# carte_pami2026.net
KiCad netlist of a schematic drawn in Altium Designer
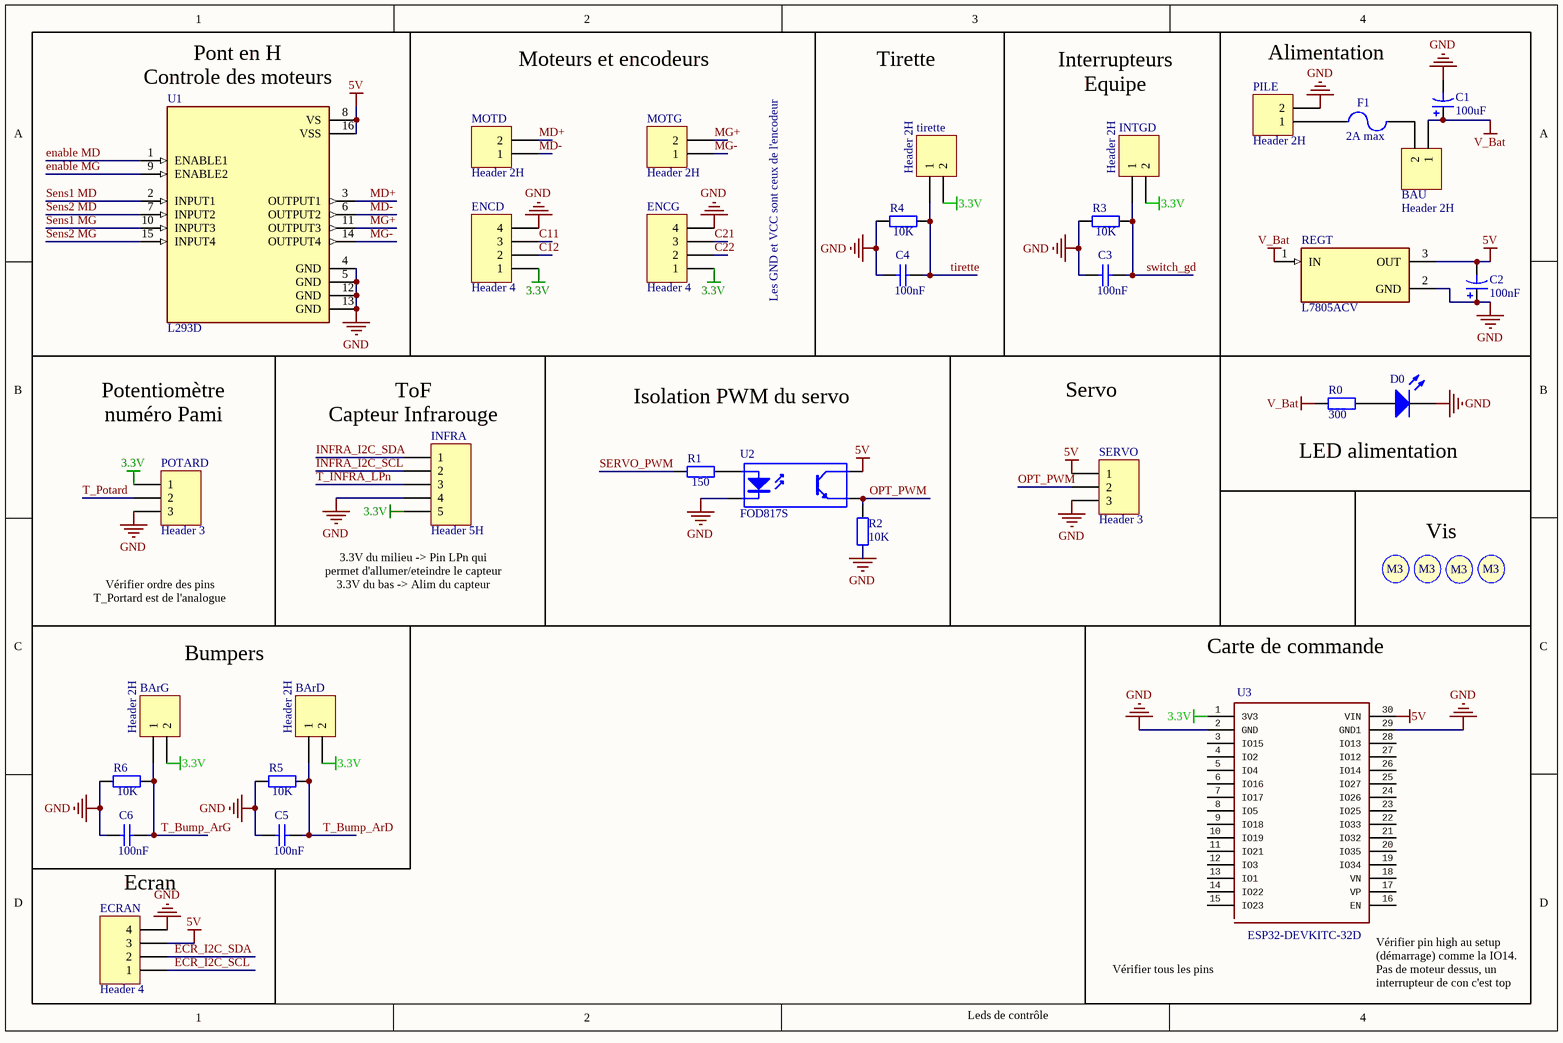
[diagram p0: carte_pami2026.SchDoc]

(export (version "E")
  (design (tool "Eeschema 10.0.6"))
  (components
    (comp (ref "BArD")
      (value "Header 2H")
      (footprint "JST_B2B-XH-A_(LF)(SN)")
      (description "Header, 2-Pin, Right Angle")
      (fields (field (name "PUBLISHER") "Altium Limited"))
      (libsource (lib "Miscellaneous Connectors") (part "Header 2H"))
    )
    (comp (ref "BArG")
      (value "Header 2H")
      (footprint "JST_B2B-XH-A_(LF)(SN)")
      (description "Header, 2-Pin, Right Angle")
      (fields (field (name "PUBLISHER") "Altium Limited"))
      (libsource (lib "Miscellaneous Connectors") (part "Header 2H"))
    )
    (comp (ref "BAU")
      (value "Header 2H")
      (footprint "JST_B2B-XH-A_(LF)(SN)")
      (description "Header, 2-Pin, Right Angle")
      (fields (field (name "PUBLISHER") "Altium Limited"))
      (libsource (lib "") (part "Header 2H_2"))
    )
    (comp (ref "C1")
      (value "100uF")
      (footprint "Condensateur")
      (description "Polarized Capacitor (Radial)")
      (fields (field (name "Comment") "35V") (field (name "PUBLISHER") "Altium Limited"))
      (libsource (lib "Miscellaneous Devices") (part "Cap Pol1"))
    )
    (comp (ref "C2")
      (value "100nF")
      (footprint "Condensateur")
      (description "Polarized Capacitor (Radial)")
      (fields (field (name "Comment") "35V") (field (name "PUBLISHER") "Altium Limited"))
      (libsource (lib "Miscellaneous Devices") (part "Cap Pol1"))
    )
    (comp (ref "C3")
      (value "100nF")
      (footprint "Capacitor 1206")
      (description "Capacitor")
      (fields (field (name "Comment") "Cap") (field (name "PUBLISHER") "Altium Limited"))
      (libsource (lib "Miscellaneous Devices") (part "Cap"))
    )
    (comp (ref "C4")
      (value "100nF")
      (footprint "Capacitor 1206")
      (description "Capacitor")
      (fields (field (name "Comment") "Cap") (field (name "PUBLISHER") "Altium Limited"))
      (libsource (lib "Miscellaneous Devices") (part "Cap"))
    )
    (comp (ref "C5")
      (value "100nF")
      (footprint "Capacitor 1206")
      (description "Capacitor")
      (fields (field (name "Comment") "Cap") (field (name "PUBLISHER") "Altium Limited"))
      (libsource (lib "Miscellaneous Devices") (part "Cap"))
    )
    (comp (ref "C6")
      (value "100nF")
      (footprint "Capacitor 1206")
      (description "Capacitor")
      (fields (field (name "Comment") "Cap") (field (name "PUBLISHER") "Altium Limited"))
      (libsource (lib "Miscellaneous Devices") (part "Cap"))
    )
    (comp (ref "D0")
      (value "L")
      (footprint "KP-3216SEC")
      (description "Typical RED, GREEN, YELLOW, AMBER GaAs LED")
      (fields (field (name "PUBLISHER") "Altium Limited"))
      (libsource (lib "Miscellaneous Devices") (part "LED2"))
    )
    (comp (ref "ECRAN")
      (value "Header 4")
      (footprint "B4BXHALFSN")
      (description "Header, 4-Pin")
      (fields (field (name "PUBLISHER") "Altium Limited"))
      (libsource (lib "Miscellaneous Connectors") (part "Header 4"))
    )
    (comp (ref "ENCD")
      (value "Header 4")
      (footprint "B4BXHALFSN")
      (description "Header, 4-Pin")
      (fields (field (name "PUBLISHER") "Altium Limited"))
      (libsource (lib "Miscellaneous Connectors") (part "Header 4"))
    )
    (comp (ref "ENCG")
      (value "Header 4")
      (footprint "B4BXHALFSN")
      (description "Header, 4-Pin")
      (fields (field (name "PUBLISHER") "Altium Limited"))
      (libsource (lib "Miscellaneous Connectors") (part "Header 4"))
    )
    (comp (ref "F1")
      (value "2A max")
      (footprint "Fuse")
      (description "Main Fuse")
      (fields (field (name "PUBLISHER") "Altium Limited"))
      (libsource (lib "Miscellaneous Devices") (part "Fuse 2"))
    )
    (comp (ref "INFRA")
      (value "Header 5H")
      (footprint "B5BXHAMLFSN")
      (description "Header, 5-Pin, Right Angle")
      (fields (field (name "PUBLISHER") "Altium Limited"))
      (libsource (lib "Miscellaneous Connectors") (part "Header 5H"))
    )
    (comp (ref "INTGD")
      (value "Header 2H")
      (footprint "JST_B2B-XH-A_(LF)(SN)")
      (description "Header, 2-Pin, Right Angle")
      (fields (field (name "PUBLISHER") "Altium Limited"))
      (libsource (lib "Miscellaneous Connectors") (part "Header 2H"))
    )
    (comp (ref "MOTD")
      (value "Header 2H")
      (footprint "JST_B2B-XH-A_(LF)(SN)")
      (description "Header, 2-Pin, Right Angle")
      (fields (field (name "PUBLISHER") "Altium Limited"))
      (libsource (lib "") (part "Header 2H_1"))
    )
    (comp (ref "MOTG")
      (value "Header 2H")
      (footprint "JST_B2B-XH-A_(LF)(SN)")
      (description "Header, 2-Pin, Right Angle")
      (fields (field (name "PUBLISHER") "Altium Limited"))
      (libsource (lib "") (part "Header 2H_1"))
    )
    (comp (ref "PILE")
      (value "Header 2H")
      (footprint "JST_B2B-XH-A_(LF)(SN)")
      (description "Header, 2-Pin, Right Angle")
      (fields (field (name "PUBLISHER") "Altium Limited"))
      (libsource (lib "") (part "Header 2H_1"))
    )
    (comp (ref "POTARD")
      (value "Header 3")
      (footprint "JST_B3B-XH-A(LF)(SN)")
      (description "Header, 3-Pin")
      (fields (field (name "PUBLISHER") "Altium Limited"))
      (libsource (lib "Miscellaneous Connectors") (part "Header 3"))
    )
    (comp (ref "R0")
      (value "300")
      (footprint "Resistor 1206")
      (description "Resistor")
      (fields (field (name "Comment") "Res2") (field (name "PUBLISHER") "Altium Limited"))
      (libsource (lib "Miscellaneous Devices") (part "Res2"))
    )
    (comp (ref "R1")
      (value "150")
      (footprint "Resistor 1206")
      (description "Resistor")
      (fields (field (name "Comment") "Res2") (field (name "PUBLISHER") "Altium Limited"))
      (libsource (lib "Miscellaneous Devices") (part "Res2"))
    )
    (comp (ref "R2")
      (value "10K")
      (footprint "Resistor 1206")
      (description "Resistor")
      (fields (field (name "Comment") "Res2") (field (name "PUBLISHER") "Altium Limited"))
      (libsource (lib "") (part "Res2_1"))
    )
    (comp (ref "R3")
      (value "10K")
      (footprint "Resistor 1206")
      (description "Resistor")
      (fields (field (name "Comment") "Res2") (field (name "PUBLISHER") "Altium Limited"))
      (libsource (lib "Miscellaneous Devices") (part "Res2"))
    )
    (comp (ref "R4")
      (value "10K")
      (footprint "Resistor 1206")
      (description "Resistor")
      (fields (field (name "Comment") "Res2") (field (name "PUBLISHER") "Altium Limited"))
      (libsource (lib "Miscellaneous Devices") (part "Res2"))
    )
    (comp (ref "R5")
      (value "10K")
      (footprint "Resistor 1206")
      (description "Resistor")
      (fields (field (name "Comment") "Res2") (field (name "PUBLISHER") "Altium Limited"))
      (libsource (lib "Miscellaneous Devices") (part "Res2"))
    )
    (comp (ref "R6")
      (value "10K")
      (footprint "Resistor 1206")
      (description "Resistor")
      (fields (field (name "Comment") "Res2") (field (name "PUBLISHER") "Altium Limited"))
      (libsource (lib "Miscellaneous Devices") (part "Res2"))
    )
    (comp (ref "REGT")
      (value "L7805ACV")
      (footprint "TO254P460X1020X1945-3P")
      (description "Linear Voltage Regulator IC Positive Fixed 1 Output 1.5A TO-220")
      (fields (field (name "MF") "STMicroelectronics"))
      (libsource (lib "L7805ACV") (part "L7805ACV"))
    )
    (comp (ref "S1")
      (value "Screw M3")
      (footprint "Screw M3")
      (libsource (lib "Robot_2019") (part "Screw M3"))
    )
    (comp (ref "S2")
      (value "Screw M3")
      (footprint "Screw M3")
      (libsource (lib "Robot_2019") (part "Screw M3"))
    )
    (comp (ref "S3")
      (value "Screw M3")
      (footprint "Screw M3")
      (libsource (lib "Robot_2019") (part "Screw M3"))
    )
    (comp (ref "S4")
      (value "Screw M3")
      (footprint "Screw M3")
      (libsource (lib "Robot_2019") (part "Screw M3"))
    )
    (comp (ref "SERVO")
      (value "Header 3")
      (footprint "JST_B3B-XH-A(LF)(SN)")
      (description "Header, 3-Pin")
      (fields (field (name "PUBLISHER") "Altium Limited"))
      (libsource (lib "Miscellaneous Connectors") (part "Header 3"))
    )
    (comp (ref "tirette")
      (value "Header 2H")
      (footprint "JST_B2B-XH-A_(LF)(SN)")
      (description "Header, 2-Pin, Right Angle")
      (fields (field (name "PUBLISHER") "Altium Limited"))
      (libsource (lib "Miscellaneous Connectors") (part "Header 2H"))
    )
    (comp (ref "U1")
      (value "L293D")
      (footprint "DIP880W50P254L2000H510Q16")
      (description "Bipolar Motor Driver - Parallel 16-PowerDIP")
      (fields (field (name "MF") "STMicroelectronics"))
      (libsource (lib "L293D") (part "L293D"))
    )
    (comp (ref "U2")
      (value "FOD817S")
      (footprint "SOP254P1016X385-4N")
      (description "4-Pin Phototransistor Optocoupler")
      (fields (field (name "PUBLISHER") "Altium Limited"))
      (libsource (lib "Miscellaneous Devices") (part "Optoisolator1"))
    )
    (comp (ref "U3")
      (value "ESP32-DEVKITC-32D")
      (footprint "MODULE_ESP32-DEVKITV1")
      (description "Eval Board For Esp-Wroom-32")
      (fields (field (name "MF") "Espressif Systems"))
      (libsource (lib "AltiumLibraryDDT") (part "ESP32-DEVKITC-32D"))
    )
  )
  (nets
    (net (code "1") (name "/C11") (class "Default")
      (node (ref "ENCD") (pin "3") (pinfunction "3_3") (pintype "passive"))
    )
    (net (code "2") (name "/C12") (class "Default")
      (node (ref "ENCD") (pin "2") (pinfunction "2_2") (pintype "passive"))
    )
    (net (code "3") (name "/C21") (class "Default")
      (node (ref "ENCG") (pin "3") (pinfunction "3_3") (pintype "passive"))
    )
    (net (code "4") (name "/C22") (class "Default")
      (node (ref "ENCG") (pin "2") (pinfunction "2_2") (pintype "passive"))
    )
    (net (code "5") (name "/ECR_I2C_SCL") (class "Default")
      (node (ref "ECRAN") (pin "1") (pinfunction "1_1") (pintype "passive"))
    )
    (net (code "6") (name "/ECR_I2C_SDA") (class "Default")
      (node (ref "ECRAN") (pin "2") (pinfunction "2_2") (pintype "passive"))
    )
    (net (code "7") (name "/INFRA_I2C_SCL") (class "Default")
      (node (ref "INFRA") (pin "2") (pinfunction "2_2") (pintype "passive"))
    )
    (net (code "8") (name "/INFRA_I2C_SDA") (class "Default")
      (node (ref "INFRA") (pin "1") (pinfunction "1_1") (pintype "passive"))
    )
    (net (code "9") (name "/MD+") (class "Default")
      (node (ref "MOTD") (pin "2") (pinfunction "2_2") (pintype "passive"))
      (node (ref "U1") (pin "3") (pinfunction "OUTPUT1_3") (pintype "output"))
    )
    (net (code "10") (name "/MD-") (class "Default")
      (node (ref "MOTD") (pin "1") (pinfunction "1_1") (pintype "passive"))
      (node (ref "U1") (pin "6") (pinfunction "OUTPUT2_6") (pintype "output"))
    )
    (net (code "11") (name "/MG+") (class "Default")
      (node (ref "MOTG") (pin "2") (pinfunction "2_2") (pintype "passive"))
      (node (ref "U1") (pin "11") (pinfunction "OUTPUT3_11") (pintype "output"))
    )
    (net (code "12") (name "/MG-") (class "Default")
      (node (ref "MOTG") (pin "1") (pinfunction "1_1") (pintype "passive"))
      (node (ref "U1") (pin "14") (pinfunction "OUTPUT4_14") (pintype "output"))
    )
    (net (code "13") (name "/OPT_PWM") (class "Default")
      (node (ref "R2") (pin "2") (pinfunction "2_2") (pintype "passive"))
      (node (ref "SERVO") (pin "2") (pinfunction "2_2") (pintype "passive"))
      (node (ref "U2") (pin "3") (pinfunction "E_3") (pintype "passive"))
    )
    (net (code "14") (name "/SERVO_PWM") (class "Default")
      (node (ref "R1") (pin "1") (pinfunction "1_1") (pintype "passive"))
    )
    (net (code "15") (name "/Sens1 MD") (class "Default")
      (node (ref "U1") (pin "2") (pinfunction "INPUT1_2") (pintype "input"))
    )
    (net (code "16") (name "/Sens1 MG") (class "Default")
      (node (ref "U1") (pin "10") (pinfunction "INPUT3_10") (pintype "input"))
    )
    (net (code "17") (name "/Sens2 MD") (class "Default")
      (node (ref "U1") (pin "7") (pinfunction "INPUT2_7") (pintype "input"))
    )
    (net (code "18") (name "/Sens2 MG") (class "Default")
      (node (ref "U1") (pin "15") (pinfunction "INPUT4_15") (pintype "input"))
    )
    (net (code "19") (name "/T_Bump_ArD") (class "Default")
      (node (ref "BArD") (pin "1") (pinfunction "1_1") (pintype "passive"))
      (node (ref "C5") (pin "2") (pinfunction "2_2") (pintype "passive"))
      (node (ref "R5") (pin "2") (pinfunction "2_2") (pintype "passive"))
    )
    (net (code "20") (name "/T_Bump_ArG") (class "Default")
      (node (ref "BArG") (pin "1") (pinfunction "1_1") (pintype "passive"))
      (node (ref "C6") (pin "2") (pinfunction "2_2") (pintype "passive"))
      (node (ref "R6") (pin "2") (pinfunction "2_2") (pintype "passive"))
    )
    (net (code "21") (name "/T_INFRA_LPn") (class "Default")
      (node (ref "INFRA") (pin "3") (pinfunction "3_3") (pintype "passive"))
    )
    (net (code "22") (name "/T_Potard") (class "Default")
      (node (ref "POTARD") (pin "2") (pinfunction "2_2") (pintype "passive"))
    )
    (net (code "23") (name "/enable MD") (class "Default")
      (node (ref "U1") (pin "1") (pinfunction "ENABLE1_1") (pintype "input"))
    )
    (net (code "24") (name "/enable MG") (class "Default")
      (node (ref "U1") (pin "9") (pinfunction "ENABLE2_9") (pintype "input"))
    )
    (net (code "25") (name "/switch_gd") (class "Default")
      (node (ref "C3") (pin "2") (pinfunction "2_2") (pintype "passive"))
      (node (ref "INTGD") (pin "1") (pinfunction "1_1") (pintype "passive"))
      (node (ref "R3") (pin "2") (pinfunction "2_2") (pintype "passive"))
    )
    (net (code "26") (name "/tirette") (class "Default")
      (node (ref "C4") (pin "2") (pinfunction "2_2") (pintype "passive"))
      (node (ref "R4") (pin "2") (pinfunction "2_2") (pintype "passive"))
      (node (ref "tirette") (pin "1") (pinfunction "1_1") (pintype "passive"))
    )
    (net (code "27") (name "3.3V") (class "Default")
      (node (ref "BArD") (pin "2") (pinfunction "2_2") (pintype "passive"))
      (node (ref "BArG") (pin "2") (pinfunction "2_2") (pintype "passive"))
      (node (ref "ENCD") (pin "1") (pinfunction "1_1") (pintype "passive"))
      (node (ref "ENCG") (pin "1") (pinfunction "1_1") (pintype "passive"))
      (node (ref "INFRA") (pin "5") (pinfunction "5_5") (pintype "passive"))
      (node (ref "INTGD") (pin "2") (pinfunction "2_2") (pintype "passive"))
      (node (ref "POTARD") (pin "1") (pinfunction "1_1") (pintype "passive"))
      (node (ref "U3") (pin "1") (pinfunction "3V3_1") (pintype "passive"))
      (node (ref "tirette") (pin "2") (pinfunction "2_2") (pintype "passive"))
    )
    (net (code "28") (name "5V") (class "Default")
      (node (ref "C2") (pin "2") (pinfunction "2_2") (pintype "passive"))
      (node (ref "ECRAN") (pin "3") (pinfunction "3_3") (pintype "passive"))
      (node (ref "REGT") (pin "3") (pinfunction "OUT_3") (pintype "power_in"))
      (node (ref "SERVO") (pin "1") (pinfunction "1_1") (pintype "passive"))
      (node (ref "U1") (pin "16") (pinfunction "VSS_16") (pintype "power_in"))
      (node (ref "U1") (pin "8") (pinfunction "VS_8") (pintype "power_in"))
      (node (ref "U2") (pin "4") (pinfunction "C_4") (pintype "passive"))
      (node (ref "U3") (pin "30") (pinfunction "VIN_30") (pintype "passive"))
    )
    (net (code "29") (name "GND") (class "Default")
      (node (ref "C1") (pin "2") (pinfunction "2_2") (pintype "passive"))
      (node (ref "C2") (pin "1") (pinfunction "1_1") (pintype "passive"))
      (node (ref "C3") (pin "1") (pinfunction "1_1") (pintype "passive"))
      (node (ref "C4") (pin "1") (pinfunction "1_1") (pintype "passive"))
      (node (ref "C5") (pin "1") (pinfunction "1_1") (pintype "passive"))
      (node (ref "C6") (pin "1") (pinfunction "1_1") (pintype "passive"))
      (node (ref "D0") (pin "2") (pinfunction "K_2") (pintype "passive"))
      (node (ref "ECRAN") (pin "4") (pinfunction "4_4") (pintype "passive"))
      (node (ref "ENCD") (pin "4") (pinfunction "4_4") (pintype "passive"))
      (node (ref "ENCG") (pin "4") (pinfunction "4_4") (pintype "passive"))
      (node (ref "INFRA") (pin "4") (pinfunction "4_4") (pintype "passive"))
      (node (ref "PILE") (pin "2") (pinfunction "2_2") (pintype "passive"))
      (node (ref "POTARD") (pin "3") (pinfunction "3_3") (pintype "passive"))
      (node (ref "R2") (pin "1") (pinfunction "1_1") (pintype "passive"))
      (node (ref "R3") (pin "1") (pinfunction "1_1") (pintype "passive"))
      (node (ref "R4") (pin "1") (pinfunction "1_1") (pintype "passive"))
      (node (ref "R5") (pin "1") (pinfunction "1_1") (pintype "passive"))
      (node (ref "R6") (pin "1") (pinfunction "1_1") (pintype "passive"))
      (node (ref "REGT") (pin "2") (pinfunction "GND_2") (pintype "power_in"))
      (node (ref "SERVO") (pin "3") (pinfunction "3_3") (pintype "passive"))
      (node (ref "U1") (pin "12") (pinfunction "GND_12") (pintype "power_in"))
      (node (ref "U1") (pin "13") (pinfunction "GND_13") (pintype "power_in"))
      (node (ref "U1") (pin "4") (pinfunction "GND_4") (pintype "power_in"))
      (node (ref "U1") (pin "5") (pinfunction "GND_5") (pintype "power_in"))
      (node (ref "U2") (pin "2") (pinfunction "K_2") (pintype "passive"))
      (node (ref "U3") (pin "2") (pinfunction "GND_2") (pintype "passive"))
      (node (ref "U3") (pin "29") (pinfunction "GND1_29") (pintype "passive"))
    )
    (net (code "30") (name "Net-(BAU-Pad2)") (class "Default")
      (node (ref "BAU") (pin "2") (pinfunction "2_2") (pintype "passive"))
      (node (ref "F1") (pin "1") (pinfunction "1_1") (pintype "passive"))
    )
    (net (code "31") (name "Net-(D0-A)") (class "Default")
      (node (ref "D0") (pin "1") (pinfunction "A_1") (pintype "passive"))
      (node (ref "R0") (pin "2") (pinfunction "2_2") (pintype "passive"))
    )
    (net (code "32") (name "Net-(F1-Pad2)") (class "Default")
      (node (ref "F1") (pin "2") (pinfunction "2_2") (pintype "passive"))
      (node (ref "PILE") (pin "1") (pinfunction "1_1") (pintype "passive"))
    )
    (net (code "33") (name "Net-(U2-A)") (class "Default")
      (node (ref "R1") (pin "2") (pinfunction "2_2") (pintype "passive"))
      (node (ref "U2") (pin "1") (pinfunction "A_1") (pintype "passive"))
    )
    (net (code "34") (name "V_Bat") (class "Default")
      (node (ref "BAU") (pin "1") (pinfunction "1_1") (pintype "passive"))
      (node (ref "C1") (pin "1") (pinfunction "1_1") (pintype "passive"))
      (node (ref "R0") (pin "1") (pinfunction "1_1") (pintype "passive"))
      (node (ref "REGT") (pin "1") (pinfunction "IN_1") (pintype "input"))
    )
    (net (code "35") (name "unconnected-(U3-EN-Pad16)") (class "Default")
      (node (ref "U3") (pin "16") (pinfunction "EN_16") (pintype "passive"))
    )
    (net (code "36") (name "unconnected-(U3-IO1-Pad13)") (class "Default")
      (node (ref "U3") (pin "13") (pinfunction "IO1_13") (pintype "passive"))
    )
    (net (code "37") (name "unconnected-(U3-IO2-Pad4)") (class "Default")
      (node (ref "U3") (pin "4") (pinfunction "IO2_4") (pintype "passive"))
    )
    (net (code "38") (name "unconnected-(U3-IO3-Pad12)") (class "Default")
      (node (ref "U3") (pin "12") (pinfunction "IO3_12") (pintype "passive"))
    )
    (net (code "39") (name "unconnected-(U3-IO4-Pad5)") (class "Default")
      (node (ref "U3") (pin "5") (pinfunction "IO4_5") (pintype "passive"))
    )
    (net (code "40") (name "unconnected-(U3-IO5-Pad8)") (class "Default")
      (node (ref "U3") (pin "8") (pinfunction "IO5_8") (pintype "passive"))
    )
    (net (code "41") (name "unconnected-(U3-IO12-Pad27)") (class "Default")
      (node (ref "U3") (pin "27") (pinfunction "IO12_27") (pintype "passive"))
    )
    (net (code "42") (name "unconnected-(U3-IO13-Pad28)") (class "Default")
      (node (ref "U3") (pin "28") (pinfunction "IO13_28") (pintype "passive"))
    )
    (net (code "43") (name "unconnected-(U3-IO14-Pad26)") (class "Default")
      (node (ref "U3") (pin "26") (pinfunction "IO14_26") (pintype "passive"))
    )
    (net (code "44") (name "unconnected-(U3-IO15-Pad3)") (class "Default")
      (node (ref "U3") (pin "3") (pinfunction "IO15_3") (pintype "passive"))
    )
    (net (code "45") (name "unconnected-(U3-IO16-Pad6)") (class "Default")
      (node (ref "U3") (pin "6") (pinfunction "IO16_6") (pintype "passive"))
    )
    (net (code "46") (name "unconnected-(U3-IO17-Pad7)") (class "Default")
      (node (ref "U3") (pin "7") (pinfunction "IO17_7") (pintype "passive"))
    )
    (net (code "47") (name "unconnected-(U3-IO18-Pad9)") (class "Default")
      (node (ref "U3") (pin "9") (pinfunction "IO18_9") (pintype "passive"))
    )
    (net (code "48") (name "unconnected-(U3-IO19-Pad10)") (class "Default")
      (node (ref "U3") (pin "10") (pinfunction "IO19_10") (pintype "passive"))
    )
    (net (code "49") (name "unconnected-(U3-IO21-Pad11)") (class "Default")
      (node (ref "U3") (pin "11") (pinfunction "IO21_11") (pintype "passive"))
    )
    (net (code "50") (name "unconnected-(U3-IO22-Pad14)") (class "Default")
      (node (ref "U3") (pin "14") (pinfunction "IO22_14") (pintype "passive"))
    )
    (net (code "51") (name "unconnected-(U3-IO23-Pad15)") (class "Default")
      (node (ref "U3") (pin "15") (pinfunction "IO23_15") (pintype "passive"))
    )
    (net (code "52") (name "unconnected-(U3-IO25-Pad23)") (class "Default")
      (node (ref "U3") (pin "23") (pinfunction "IO25_23") (pintype "passive"))
    )
    (net (code "53") (name "unconnected-(U3-IO26-Pad24)") (class "Default")
      (node (ref "U3") (pin "24") (pinfunction "IO26_24") (pintype "passive"))
    )
    (net (code "54") (name "unconnected-(U3-IO27-Pad25)") (class "Default")
      (node (ref "U3") (pin "25") (pinfunction "IO27_25") (pintype "passive"))
    )
    (net (code "55") (name "unconnected-(U3-IO32-Pad21)") (class "Default")
      (node (ref "U3") (pin "21") (pinfunction "IO32_21") (pintype "passive"))
    )
    (net (code "56") (name "unconnected-(U3-IO33-Pad22)") (class "Default")
      (node (ref "U3") (pin "22") (pinfunction "IO33_22") (pintype "passive"))
    )
    (net (code "57") (name "unconnected-(U3-IO34-Pad19)") (class "Default")
      (node (ref "U3") (pin "19") (pinfunction "IO34_19") (pintype "passive"))
    )
    (net (code "58") (name "unconnected-(U3-IO35-Pad20)") (class "Default")
      (node (ref "U3") (pin "20") (pinfunction "IO35_20") (pintype "passive"))
    )
    (net (code "59") (name "unconnected-(U3-VN-Pad18)") (class "Default")
      (node (ref "U3") (pin "18") (pinfunction "VN_18") (pintype "passive"))
    )
    (net (code "60") (name "unconnected-(U3-VP-Pad17)") (class "Default")
      (node (ref "U3") (pin "17") (pinfunction "VP_17") (pintype "passive"))
    )
  )
)
